# bio_dnt_adc_filter.net
KiCad netlist of a schematic drawn in Altium Designer
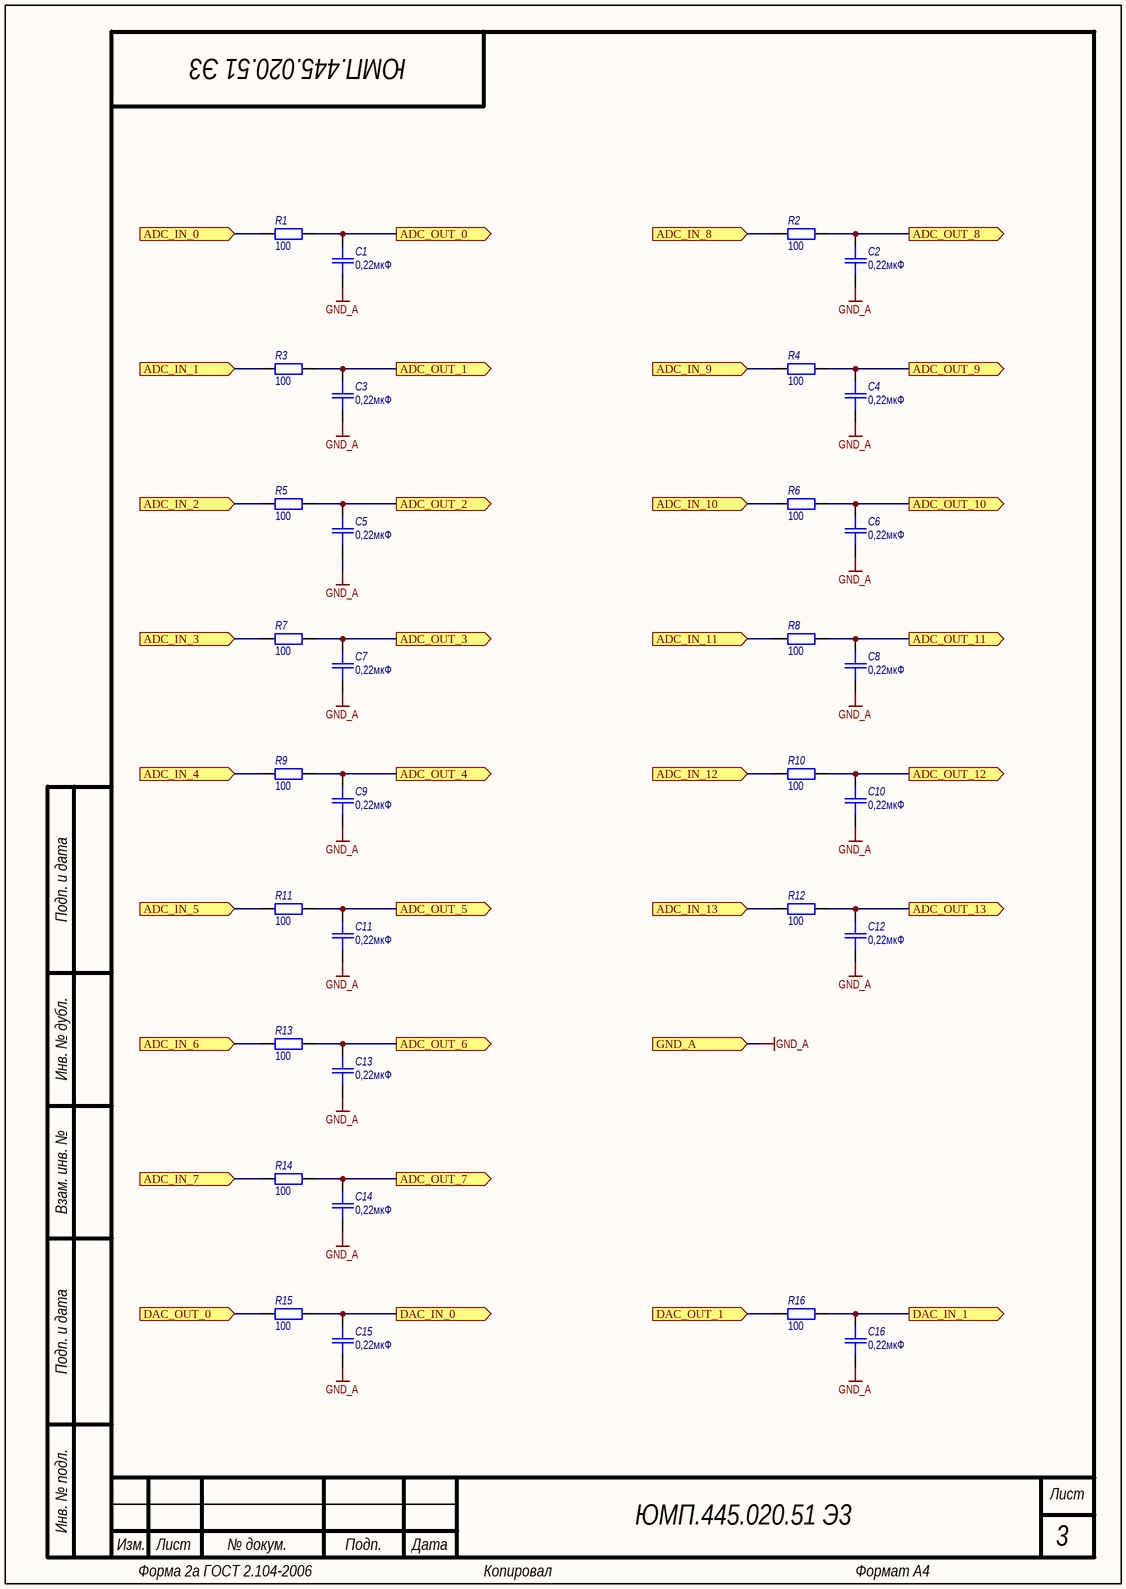
[diagram p0: bio_dnt_adc_filter.SchDoc]

(export (version "E")
  (design (tool "Eeschema 10.0.6"))
  (components
    (comp (ref "C1")
      (value "0,22мкФ")
      (footprint "CR-0805")
      (description "Конденсатор для поверхностного монтажа")
      (libsource (lib "my_passive") (part "C_smd"))
    )
    (comp (ref "C2")
      (value "0,22мкФ")
      (footprint "CR-0805")
      (description "Конденсатор для поверхностного монтажа")
      (libsource (lib "my_passive") (part "C_smd"))
    )
    (comp (ref "C3")
      (value "0,22мкФ")
      (footprint "CR-0805")
      (description "Конденсатор для поверхностного монтажа")
      (libsource (lib "my_passive") (part "C_smd"))
    )
    (comp (ref "C4")
      (value "0,22мкФ")
      (footprint "CR-0805")
      (description "Конденсатор для поверхностного монтажа")
      (libsource (lib "my_passive") (part "C_smd"))
    )
    (comp (ref "C5")
      (value "0,22мкФ")
      (footprint "CR-0805")
      (description "Конденсатор для поверхностного монтажа")
      (libsource (lib "my_passive") (part "C_smd"))
    )
    (comp (ref "C6")
      (value "0,22мкФ")
      (footprint "CR-0805")
      (description "Конденсатор для поверхностного монтажа")
      (libsource (lib "my_passive") (part "C_smd"))
    )
    (comp (ref "C7")
      (value "0,22мкФ")
      (footprint "CR-0805")
      (description "Конденсатор для поверхностного монтажа")
      (libsource (lib "my_passive") (part "C_smd"))
    )
    (comp (ref "C8")
      (value "0,22мкФ")
      (footprint "CR-0805")
      (description "Конденсатор для поверхностного монтажа")
      (libsource (lib "my_passive") (part "C_smd"))
    )
    (comp (ref "C9")
      (value "0,22мкФ")
      (footprint "CR-0805")
      (description "Конденсатор для поверхностного монтажа")
      (libsource (lib "my_passive") (part "C_smd"))
    )
    (comp (ref "C10")
      (value "0,22мкФ")
      (footprint "CR-0805")
      (description "Конденсатор для поверхностного монтажа")
      (libsource (lib "my_passive") (part "C_smd"))
    )
    (comp (ref "C11")
      (value "0,22мкФ")
      (footprint "CR-0805")
      (description "Конденсатор для поверхностного монтажа")
      (libsource (lib "my_passive") (part "C_smd"))
    )
    (comp (ref "C12")
      (value "0,22мкФ")
      (footprint "CR-0805")
      (description "Конденсатор для поверхностного монтажа")
      (libsource (lib "my_passive") (part "C_smd"))
    )
    (comp (ref "C13")
      (value "0,22мкФ")
      (footprint "CR-0805")
      (description "Конденсатор для поверхностного монтажа")
      (libsource (lib "my_passive") (part "C_smd"))
    )
    (comp (ref "C14")
      (value "0,22мкФ")
      (footprint "CR-0805")
      (description "Конденсатор для поверхностного монтажа")
      (libsource (lib "my_passive") (part "C_smd"))
    )
    (comp (ref "C15")
      (value "0,22мкФ")
      (footprint "CR-0805")
      (description "Конденсатор для поверхностного монтажа")
      (libsource (lib "my_passive") (part "C_smd"))
    )
    (comp (ref "C16")
      (value "0,22мкФ")
      (footprint "CR-0805")
      (description "Конденсатор для поверхностного монтажа")
      (libsource (lib "my_passive") (part "C_smd"))
    )
    (comp (ref "R1")
      (value "100")
      (footprint "CR-0805")
      (description "Резистор для поверхностного монтажа")
      (libsource (lib "my_passive") (part "R_smd"))
    )
    (comp (ref "R2")
      (value "100")
      (footprint "CR-0805")
      (description "Резистор для поверхностного монтажа")
      (libsource (lib "my_passive") (part "R_smd"))
    )
    (comp (ref "R3")
      (value "100")
      (footprint "CR-0805")
      (description "Резистор для поверхностного монтажа")
      (libsource (lib "my_passive") (part "R_smd"))
    )
    (comp (ref "R4")
      (value "100")
      (footprint "CR-0805")
      (description "Резистор для поверхностного монтажа")
      (libsource (lib "my_passive") (part "R_smd"))
    )
    (comp (ref "R5")
      (value "100")
      (footprint "CR-0805")
      (description "Резистор для поверхностного монтажа")
      (libsource (lib "my_passive") (part "R_smd"))
    )
    (comp (ref "R6")
      (value "100")
      (footprint "CR-0805")
      (description "Резистор для поверхностного монтажа")
      (libsource (lib "my_passive") (part "R_smd"))
    )
    (comp (ref "R7")
      (value "100")
      (footprint "CR-0805")
      (description "Резистор для поверхностного монтажа")
      (libsource (lib "my_passive") (part "R_smd"))
    )
    (comp (ref "R8")
      (value "100")
      (footprint "CR-0805")
      (description "Резистор для поверхностного монтажа")
      (libsource (lib "my_passive") (part "R_smd"))
    )
    (comp (ref "R9")
      (value "100")
      (footprint "CR-0805")
      (description "Резистор для поверхностного монтажа")
      (libsource (lib "my_passive") (part "R_smd"))
    )
    (comp (ref "R10")
      (value "100")
      (footprint "CR-0805")
      (description "Резистор для поверхностного монтажа")
      (libsource (lib "my_passive") (part "R_smd"))
    )
    (comp (ref "R11")
      (value "100")
      (footprint "CR-0805")
      (description "Резистор для поверхностного монтажа")
      (libsource (lib "my_passive") (part "R_smd"))
    )
    (comp (ref "R12")
      (value "100")
      (footprint "CR-0805")
      (description "Резистор для поверхностного монтажа")
      (libsource (lib "my_passive") (part "R_smd"))
    )
    (comp (ref "R13")
      (value "100")
      (footprint "CR-0805")
      (description "Резистор для поверхностного монтажа")
      (libsource (lib "my_passive") (part "R_smd"))
    )
    (comp (ref "R14")
      (value "100")
      (footprint "CR-0805")
      (description "Резистор для поверхностного монтажа")
      (libsource (lib "my_passive") (part "R_smd"))
    )
    (comp (ref "R15")
      (value "100")
      (footprint "CR-0805")
      (description "Резистор для поверхностного монтажа")
      (libsource (lib "my_passive") (part "R_smd"))
    )
    (comp (ref "R16")
      (value "100")
      (footprint "CR-0805")
      (description "Резистор для поверхностного монтажа")
      (libsource (lib "my_passive") (part "R_smd"))
    )
  )
  (nets
    (net (code "1") (name "/ADC_IN_0") (class "Default")
      (node (ref "R1") (pin "2") (pinfunction "2_2") (pintype "passive"))
    )
    (net (code "2") (name "/ADC_IN_1") (class "Default")
      (node (ref "R3") (pin "2") (pinfunction "2_2") (pintype "passive"))
    )
    (net (code "3") (name "/ADC_IN_2") (class "Default")
      (node (ref "R5") (pin "2") (pinfunction "2_2") (pintype "passive"))
    )
    (net (code "4") (name "/ADC_IN_3") (class "Default")
      (node (ref "R7") (pin "2") (pinfunction "2_2") (pintype "passive"))
    )
    (net (code "5") (name "/ADC_IN_4") (class "Default")
      (node (ref "R9") (pin "2") (pinfunction "2_2") (pintype "passive"))
    )
    (net (code "6") (name "/ADC_IN_5") (class "Default")
      (node (ref "R11") (pin "2") (pinfunction "2_2") (pintype "passive"))
    )
    (net (code "7") (name "/ADC_IN_6") (class "Default")
      (node (ref "R13") (pin "2") (pinfunction "2_2") (pintype "passive"))
    )
    (net (code "8") (name "/ADC_IN_7") (class "Default")
      (node (ref "R14") (pin "2") (pinfunction "2_2") (pintype "passive"))
    )
    (net (code "9") (name "/ADC_IN_8") (class "Default")
      (node (ref "R2") (pin "2") (pinfunction "2_2") (pintype "passive"))
    )
    (net (code "10") (name "/ADC_IN_9") (class "Default")
      (node (ref "R4") (pin "2") (pinfunction "2_2") (pintype "passive"))
    )
    (net (code "11") (name "/ADC_IN_10") (class "Default")
      (node (ref "R6") (pin "2") (pinfunction "2_2") (pintype "passive"))
    )
    (net (code "12") (name "/ADC_IN_11") (class "Default")
      (node (ref "R8") (pin "2") (pinfunction "2_2") (pintype "passive"))
    )
    (net (code "13") (name "/ADC_IN_12") (class "Default")
      (node (ref "R10") (pin "2") (pinfunction "2_2") (pintype "passive"))
    )
    (net (code "14") (name "/ADC_IN_13") (class "Default")
      (node (ref "R12") (pin "2") (pinfunction "2_2") (pintype "passive"))
    )
    (net (code "15") (name "/ADC_OUT_0") (class "Default")
      (node (ref "C1") (pin "2") (pinfunction "2_2") (pintype "passive"))
      (node (ref "R1") (pin "1") (pinfunction "1_1") (pintype "passive"))
    )
    (net (code "16") (name "/ADC_OUT_1") (class "Default")
      (node (ref "C3") (pin "2") (pinfunction "2_2") (pintype "passive"))
      (node (ref "R3") (pin "1") (pinfunction "1_1") (pintype "passive"))
    )
    (net (code "17") (name "/ADC_OUT_2") (class "Default")
      (node (ref "C5") (pin "2") (pinfunction "2_2") (pintype "passive"))
      (node (ref "R5") (pin "1") (pinfunction "1_1") (pintype "passive"))
    )
    (net (code "18") (name "/ADC_OUT_3") (class "Default")
      (node (ref "C7") (pin "2") (pinfunction "2_2") (pintype "passive"))
      (node (ref "R7") (pin "1") (pinfunction "1_1") (pintype "passive"))
    )
    (net (code "19") (name "/ADC_OUT_4") (class "Default")
      (node (ref "C9") (pin "2") (pinfunction "2_2") (pintype "passive"))
      (node (ref "R9") (pin "1") (pinfunction "1_1") (pintype "passive"))
    )
    (net (code "20") (name "/ADC_OUT_5") (class "Default")
      (node (ref "C11") (pin "2") (pinfunction "2_2") (pintype "passive"))
      (node (ref "R11") (pin "1") (pinfunction "1_1") (pintype "passive"))
    )
    (net (code "21") (name "/ADC_OUT_6") (class "Default")
      (node (ref "C13") (pin "2") (pinfunction "2_2") (pintype "passive"))
      (node (ref "R13") (pin "1") (pinfunction "1_1") (pintype "passive"))
    )
    (net (code "22") (name "/ADC_OUT_7") (class "Default")
      (node (ref "C14") (pin "2") (pinfunction "2_2") (pintype "passive"))
      (node (ref "R14") (pin "1") (pinfunction "1_1") (pintype "passive"))
    )
    (net (code "23") (name "/ADC_OUT_8") (class "Default")
      (node (ref "C2") (pin "2") (pinfunction "2_2") (pintype "passive"))
      (node (ref "R2") (pin "1") (pinfunction "1_1") (pintype "passive"))
    )
    (net (code "24") (name "/ADC_OUT_9") (class "Default")
      (node (ref "C4") (pin "2") (pinfunction "2_2") (pintype "passive"))
      (node (ref "R4") (pin "1") (pinfunction "1_1") (pintype "passive"))
    )
    (net (code "25") (name "/ADC_OUT_10") (class "Default")
      (node (ref "C6") (pin "2") (pinfunction "2_2") (pintype "passive"))
      (node (ref "R6") (pin "1") (pinfunction "1_1") (pintype "passive"))
    )
    (net (code "26") (name "/ADC_OUT_11") (class "Default")
      (node (ref "C8") (pin "2") (pinfunction "2_2") (pintype "passive"))
      (node (ref "R8") (pin "1") (pinfunction "1_1") (pintype "passive"))
    )
    (net (code "27") (name "/ADC_OUT_12") (class "Default")
      (node (ref "C10") (pin "2") (pinfunction "2_2") (pintype "passive"))
      (node (ref "R10") (pin "1") (pinfunction "1_1") (pintype "passive"))
    )
    (net (code "28") (name "/ADC_OUT_13") (class "Default")
      (node (ref "C12") (pin "2") (pinfunction "2_2") (pintype "passive"))
      (node (ref "R12") (pin "1") (pinfunction "1_1") (pintype "passive"))
    )
    (net (code "29") (name "/DAC_IN_0") (class "Default")
      (node (ref "C15") (pin "2") (pinfunction "2_2") (pintype "passive"))
      (node (ref "R15") (pin "1") (pinfunction "1_1") (pintype "passive"))
    )
    (net (code "30") (name "/DAC_IN_1") (class "Default")
      (node (ref "C16") (pin "2") (pinfunction "2_2") (pintype "passive"))
      (node (ref "R16") (pin "1") (pinfunction "1_1") (pintype "passive"))
    )
    (net (code "31") (name "/DAC_OUT_0") (class "Default")
      (node (ref "R15") (pin "2") (pinfunction "2_2") (pintype "passive"))
    )
    (net (code "32") (name "/DAC_OUT_1") (class "Default")
      (node (ref "R16") (pin "2") (pinfunction "2_2") (pintype "passive"))
    )
    (net (code "33") (name "GND_A") (class "Default")
      (node (ref "C1") (pin "1") (pinfunction "1_1") (pintype "passive"))
      (node (ref "C10") (pin "1") (pinfunction "1_1") (pintype "passive"))
      (node (ref "C11") (pin "1") (pinfunction "1_1") (pintype "passive"))
      (node (ref "C12") (pin "1") (pinfunction "1_1") (pintype "passive"))
      (node (ref "C13") (pin "1") (pinfunction "1_1") (pintype "passive"))
      (node (ref "C14") (pin "1") (pinfunction "1_1") (pintype "passive"))
      (node (ref "C15") (pin "1") (pinfunction "1_1") (pintype "passive"))
      (node (ref "C16") (pin "1") (pinfunction "1_1") (pintype "passive"))
      (node (ref "C2") (pin "1") (pinfunction "1_1") (pintype "passive"))
      (node (ref "C3") (pin "1") (pinfunction "1_1") (pintype "passive"))
      (node (ref "C4") (pin "1") (pinfunction "1_1") (pintype "passive"))
      (node (ref "C5") (pin "1") (pinfunction "1_1") (pintype "passive"))
      (node (ref "C6") (pin "1") (pinfunction "1_1") (pintype "passive"))
      (node (ref "C7") (pin "1") (pinfunction "1_1") (pintype "passive"))
      (node (ref "C8") (pin "1") (pinfunction "1_1") (pintype "passive"))
      (node (ref "C9") (pin "1") (pinfunction "1_1") (pintype "passive"))
    )
  )
)
